# Comparator-Sampler.net
KiCad netlist of a schematic drawn in Altium Designer
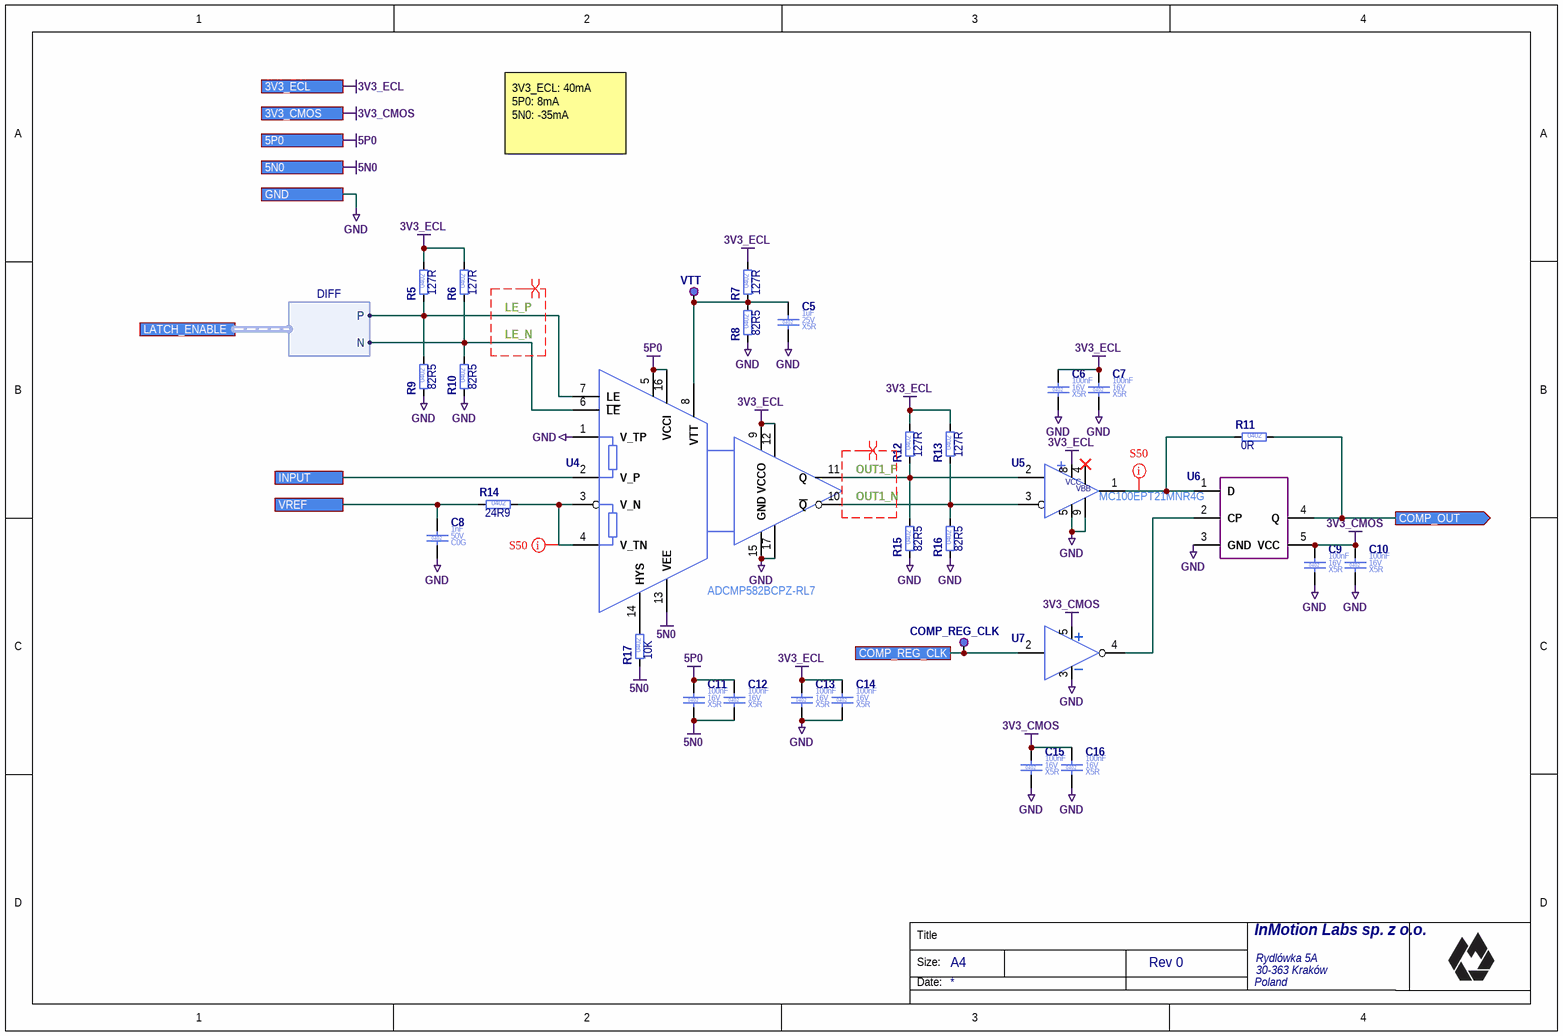
[diagram p0: Comparator-Sampler.SchDoc]

(export (version "E")
  (design (tool "Eeschema 10.0.6"))
  (components
    (comp (ref "C5")
      (value "C_1UF_25V_X5R_0402_10")
      (footprint "C_0402_1005")
      (description "Ceramic Capacitor")
      (fields
        (field (name "CASE/PACKAGE") "0402")
        (field (name "VOLTAGE RATING (DC)") "25V")
        (field (name "DIELECTRIC") "X5R")
        (field (name "CAPACITANCE") "1uF")
        (field (name "TOLERANCE") "10%")
        (field (name "MANUFACTURER PART NUMBER") "CL05A105KA5NQNC")
      )
      (libsource (lib "7Sigma") (part "C"))
    )
    (comp (ref "C6")
      (value "C_100NF_16V_X5R_0402_10")
      (footprint "C_0402_1005")
      (description "Ceramic Capacitor")
      (fields
        (field (name "CASE/PACKAGE") "0402")
        (field (name "VOLTAGE RATING (DC)") "16V")
        (field (name "DIELECTRIC") "X5R")
        (field (name "CAPACITANCE") "100nF")
        (field (name "TOLERANCE") "10%")
        (field (name "MANUFACTURER PART NUMBER") "EMK105BJ104KV-F")
      )
      (libsource (lib "7Sigma") (part "C"))
    )
    (comp (ref "C7")
      (value "C_100NF_16V_X5R_0402_10")
      (footprint "C_0402_1005")
      (description "Ceramic Capacitor")
      (fields
        (field (name "CASE/PACKAGE") "0402")
        (field (name "VOLTAGE RATING (DC)") "16V")
        (field (name "DIELECTRIC") "X5R")
        (field (name "CAPACITANCE") "100nF")
        (field (name "TOLERANCE") "10%")
        (field (name "MANUFACTURER PART NUMBER") "EMK105BJ104KV-F")
      )
      (libsource (lib "7Sigma") (part "C"))
    )
    (comp (ref "C8")
      (value "C_1NF_50V_C0G_0402_5")
      (footprint "C_0402_1005")
      (description "Ceramic Capacitor")
      (fields
        (field (name "CASE/PACKAGE") "0402")
        (field (name "VOLTAGE RATING (DC)") "50V")
        (field (name "DIELECTRIC") "C0G")
        (field (name "CAPACITANCE") "1nF")
        (field (name "TOLERANCE") "5%")
        (field (name "MANUFACTURER PART NUMBER") "UMK105CG102JV-F")
      )
      (libsource (lib "7Sigma") (part "C"))
    )
    (comp (ref "C9")
      (value "C_100NF_16V_X5R_0402_10")
      (footprint "C_0402_1005")
      (description "Ceramic Capacitor")
      (fields
        (field (name "CASE/PACKAGE") "0402")
        (field (name "VOLTAGE RATING (DC)") "16V")
        (field (name "DIELECTRIC") "X5R")
        (field (name "CAPACITANCE") "100nF")
        (field (name "TOLERANCE") "10%")
        (field (name "MANUFACTURER PART NUMBER") "EMK105BJ104KV-F")
      )
      (libsource (lib "7Sigma") (part "C"))
    )
    (comp (ref "C10")
      (value "C_100NF_16V_X5R_0402_10")
      (footprint "C_0402_1005")
      (description "Ceramic Capacitor")
      (fields
        (field (name "CASE/PACKAGE") "0402")
        (field (name "VOLTAGE RATING (DC)") "16V")
        (field (name "DIELECTRIC") "X5R")
        (field (name "CAPACITANCE") "100nF")
        (field (name "TOLERANCE") "10%")
        (field (name "MANUFACTURER PART NUMBER") "EMK105BJ104KV-F")
      )
      (libsource (lib "7Sigma") (part "C"))
    )
    (comp (ref "C11")
      (value "C_100NF_16V_X5R_0402_10")
      (footprint "C_0402_1005")
      (description "Ceramic Capacitor")
      (fields
        (field (name "CASE/PACKAGE") "0402")
        (field (name "VOLTAGE RATING (DC)") "16V")
        (field (name "DIELECTRIC") "X5R")
        (field (name "CAPACITANCE") "100nF")
        (field (name "TOLERANCE") "10%")
        (field (name "MANUFACTURER PART NUMBER") "EMK105BJ104KV-F")
      )
      (libsource (lib "7Sigma") (part "C"))
    )
    (comp (ref "C12")
      (value "C_100NF_16V_X5R_0402_10")
      (footprint "C_0402_1005")
      (description "Ceramic Capacitor")
      (fields
        (field (name "CASE/PACKAGE") "0402")
        (field (name "VOLTAGE RATING (DC)") "16V")
        (field (name "DIELECTRIC") "X5R")
        (field (name "CAPACITANCE") "100nF")
        (field (name "TOLERANCE") "10%")
        (field (name "MANUFACTURER PART NUMBER") "EMK105BJ104KV-F")
      )
      (libsource (lib "7Sigma") (part "C"))
    )
    (comp (ref "C13")
      (value "C_100NF_16V_X5R_0402_10")
      (footprint "C_0402_1005")
      (description "Ceramic Capacitor")
      (fields
        (field (name "CASE/PACKAGE") "0402")
        (field (name "VOLTAGE RATING (DC)") "16V")
        (field (name "DIELECTRIC") "X5R")
        (field (name "CAPACITANCE") "100nF")
        (field (name "TOLERANCE") "10%")
        (field (name "MANUFACTURER PART NUMBER") "EMK105BJ104KV-F")
      )
      (libsource (lib "7Sigma") (part "C"))
    )
    (comp (ref "C14")
      (value "C_100NF_16V_X5R_0402_10")
      (footprint "C_0402_1005")
      (description "Ceramic Capacitor")
      (fields
        (field (name "CASE/PACKAGE") "0402")
        (field (name "VOLTAGE RATING (DC)") "16V")
        (field (name "DIELECTRIC") "X5R")
        (field (name "CAPACITANCE") "100nF")
        (field (name "TOLERANCE") "10%")
        (field (name "MANUFACTURER PART NUMBER") "EMK105BJ104KV-F")
      )
      (libsource (lib "7Sigma") (part "C"))
    )
    (comp (ref "C15")
      (value "C_100NF_16V_X5R_0402_10")
      (footprint "C_0402_1005")
      (description "Ceramic Capacitor")
      (fields
        (field (name "CASE/PACKAGE") "0402")
        (field (name "VOLTAGE RATING (DC)") "16V")
        (field (name "DIELECTRIC") "X5R")
        (field (name "CAPACITANCE") "100nF")
        (field (name "TOLERANCE") "10%")
        (field (name "MANUFACTURER PART NUMBER") "EMK105BJ104KV-F")
      )
      (libsource (lib "7Sigma") (part "C"))
    )
    (comp (ref "C16")
      (value "C_100NF_16V_X5R_0402_10")
      (footprint "C_0402_1005")
      (description "Ceramic Capacitor")
      (fields
        (field (name "CASE/PACKAGE") "0402")
        (field (name "VOLTAGE RATING (DC)") "16V")
        (field (name "DIELECTRIC") "X5R")
        (field (name "CAPACITANCE") "100nF")
        (field (name "TOLERANCE") "10%")
        (field (name "MANUFACTURER PART NUMBER") "EMK105BJ104KV-F")
      )
      (libsource (lib "7Sigma") (part "C"))
    )
    (comp (ref "COMP_REG_CLK")
      (value "TP_PAD_1.3MM")
      (footprint "TP_PAD_1.3MM")
      (description "Testpoint SMD 1.3mm")
      (libsource (lib "7Sigma") (part "TESTPOINT"))
    )
    (comp (ref "R5")
      (value "R_127R_0402_1")
      (footprint "R_0402_1005")
      (description "Thick Film Resistor")
      (fields
        (field (name "RESISTANCE") "127R")
        (field (name "CASE/PACKAGE") "0402")
        (field (name "TOLERANCE") "1%")
        (field (name "MANUFACTURER") "Yageo")
      )
      (libsource (lib "7Sigma") (part "R"))
    )
    (comp (ref "R6")
      (value "R_127R_0402_1")
      (footprint "R_0402_1005")
      (description "Thick Film Resistor")
      (fields
        (field (name "RESISTANCE") "127R")
        (field (name "CASE/PACKAGE") "0402")
        (field (name "TOLERANCE") "1%")
        (field (name "MANUFACTURER") "Yageo")
      )
      (libsource (lib "7Sigma") (part "R"))
    )
    (comp (ref "R7")
      (value "R_127R_0402_1")
      (footprint "R_0402_1005")
      (description "Thick Film Resistor")
      (fields
        (field (name "RESISTANCE") "127R")
        (field (name "CASE/PACKAGE") "0402")
        (field (name "TOLERANCE") "1%")
        (field (name "MANUFACTURER") "Yageo")
      )
      (libsource (lib "7Sigma") (part "R"))
    )
    (comp (ref "R8")
      (value "R_82R5_0402_1")
      (footprint "R_0402_1005")
      (description "Thick Film Resistor")
      (fields
        (field (name "RESISTANCE") "82R5")
        (field (name "CASE/PACKAGE") "0402")
        (field (name "TOLERANCE") "1%")
        (field (name "MANUFACTURER") "Yageo")
      )
      (libsource (lib "7Sigma") (part "R"))
    )
    (comp (ref "R9")
      (value "R_82R5_0402_1")
      (footprint "R_0402_1005")
      (description "Thick Film Resistor")
      (fields
        (field (name "RESISTANCE") "82R5")
        (field (name "CASE/PACKAGE") "0402")
        (field (name "TOLERANCE") "1%")
        (field (name "MANUFACTURER") "Yageo")
      )
      (libsource (lib "7Sigma") (part "R"))
    )
    (comp (ref "R10")
      (value "R_82R5_0402_1")
      (footprint "R_0402_1005")
      (description "Thick Film Resistor")
      (fields
        (field (name "RESISTANCE") "82R5")
        (field (name "CASE/PACKAGE") "0402")
        (field (name "TOLERANCE") "1%")
        (field (name "MANUFACTURER") "Yageo")
      )
      (libsource (lib "7Sigma") (part "R"))
    )
    (comp (ref "R11")
      (value "R_0R_0402_1")
      (footprint "R_0402_1005")
      (description "Thick Film Resistor")
      (fields
        (field (name "RESISTANCE") "0R")
        (field (name "CASE/PACKAGE") "0402")
        (field (name "TOLERANCE") "1%")
        (field (name "MANUFACTURER") "Yageo")
      )
      (libsource (lib "7Sigma") (part "R"))
    )
    (comp (ref "R12")
      (value "R_127R_0402_1")
      (footprint "R_0402_1005")
      (description "Thick Film Resistor")
      (fields
        (field (name "RESISTANCE") "127R")
        (field (name "CASE/PACKAGE") "0402")
        (field (name "TOLERANCE") "1%")
        (field (name "MANUFACTURER") "Yageo")
      )
      (libsource (lib "7Sigma") (part "R"))
    )
    (comp (ref "R13")
      (value "R_127R_0402_1")
      (footprint "R_0402_1005")
      (description "Thick Film Resistor")
      (fields
        (field (name "RESISTANCE") "127R")
        (field (name "CASE/PACKAGE") "0402")
        (field (name "TOLERANCE") "1%")
        (field (name "MANUFACTURER") "Yageo")
      )
      (libsource (lib "7Sigma") (part "R"))
    )
    (comp (ref "R14")
      (value "R_24R9_0402_1")
      (footprint "R_0402_1005")
      (description "Thick Film Resistor")
      (fields
        (field (name "RESISTANCE") "24R9")
        (field (name "CASE/PACKAGE") "0402")
        (field (name "TOLERANCE") "1%")
        (field (name "MANUFACTURER") "Yageo")
      )
      (libsource (lib "7Sigma") (part "R"))
    )
    (comp (ref "R15")
      (value "R_82R5_0402_1")
      (footprint "R_0402_1005")
      (description "Thick Film Resistor")
      (fields
        (field (name "RESISTANCE") "82R5")
        (field (name "CASE/PACKAGE") "0402")
        (field (name "TOLERANCE") "1%")
        (field (name "MANUFACTURER") "Yageo")
      )
      (libsource (lib "7Sigma") (part "R"))
    )
    (comp (ref "R16")
      (value "R_82R5_0402_1")
      (footprint "R_0402_1005")
      (description "Thick Film Resistor")
      (fields
        (field (name "RESISTANCE") "82R5")
        (field (name "CASE/PACKAGE") "0402")
        (field (name "TOLERANCE") "1%")
        (field (name "MANUFACTURER") "Yageo")
      )
      (libsource (lib "7Sigma") (part "R"))
    )
    (comp (ref "R17")
      (value "R_10K_0402_1")
      (footprint "R_0402_1005")
      (description "Thick Film Resistor")
      (fields
        (field (name "RESISTANCE") "10K")
        (field (name "CASE/PACKAGE") "0402")
        (field (name "TOLERANCE") "1%")
        (field (name "MANUFACTURER") "Yageo")
      )
      (libsource (lib "7Sigma") (part "R"))
    )
    (comp (ref "U4")
      (value "ADCMP582BCPZ-RL7")
      (footprint "QFN50P300X300X100_HS-17N")
      (description "Single Comparator")
      (fields
        (field (name "MANUFACTURER PART NUMBER") "ADCMP582BCPZ-RL7")
        (field (name "MANUFACTURER") "Analog Devices")
      )
      (libsource (lib "7Sigma") (part "ADCMP582"))
    )
    (comp (ref "U5")
      (value "MC100EPT21MNR4G")
      (footprint "SON50P200X80_HS-9N")
      (description "Differential LVPECL/LVDS/CML to LVTTL/LVCMOS Translator")
      (fields
        (field (name "MANUFACTURER") "ON Semiconductor")
        (field (name "MANUFACTURER PART NUMBER") "MC100EPT21MNR4G")
      )
      (libsource (lib "7Sigma") (part "MC100EPT21"))
    )
    (comp (ref "U6")
      (value "74LVC1G79GV,125")
      (footprint "SOT23-5_SC74A_SOT753_M")
      (description "D Flip Flop Positive Edge Trigger")
      (fields (field (name "MANUFACTURER") "Nexperia"))
      (libsource (lib "7Sigma") (part "74LVC1G79"))
    )
    (comp (ref "U7")
      (value "SN74AHC1G04DBVR")
      (footprint "SOT23-5_SC74A_SOT753_M")
      (description "Inverters Single")
      (fields (field (name "MANUFACTURER") "Texas Instruments"))
      (libsource (lib "7Sigma") (part "SN74AHC1G04DBVR"))
    )
    (comp (ref "VTT")
      (value "TP_PAD_1.3MM")
      (footprint "TP_PAD_1.3MM")
      (description "Testpoint SMD 1.3mm")
      (libsource (lib "7Sigma") (part "TESTPOINT"))
    )
  )
  (nets
    (net (code "2") (name "/COMP_OUT") (class "Default")
      (node (ref "R11") (pin "2") (pinfunction "2_2") (pintype "passive"))
      (node (ref "U6") (pin "4") (pinfunction "Q_4") (pintype "passive"))
    )
    (net (code "3") (name "/COMP_REG_CLK") (class "Default")
      (node (ref "COMP_REG_CLK") (pin "1") (pinfunction "TP_1") (pintype "passive"))
      (node (ref "U7") (pin "2") (pinfunction "2_2") (pintype "passive"))
    )
    (net (code "4") (name "/INPUT") (class "Default")
      (node (ref "U4") (pin "2") (pinfunction "V_P_2") (pintype "passive"))
    )
    (net (code "5") (name "/LE_N") (class "Default")
      (node (ref "R10") (pin "2") (pinfunction "2_2") (pintype "passive"))
      (node (ref "R6") (pin "1") (pinfunction "1_1") (pintype "passive"))
      (node (ref "U4") (pin "6") (pinfunction "LE_6") (pintype "passive"))
    )
    (net (code "6") (name "/LE_P") (class "Default")
      (node (ref "R5") (pin "1") (pinfunction "1_1") (pintype "passive"))
      (node (ref "R9") (pin "2") (pinfunction "2_2") (pintype "passive"))
      (node (ref "U4") (pin "7") (pinfunction "LE_7") (pintype "passive"))
    )
    (net (code "7") (name "/OUT1_N") (class "Default")
      (node (ref "R13") (pin "1") (pinfunction "1_1") (pintype "passive"))
      (node (ref "R16") (pin "2") (pinfunction "2_2") (pintype "passive"))
      (node (ref "U4") (pin "10") (pinfunction "Q_10") (pintype "passive"))
      (node (ref "U5") (pin "3") (pinfunction "D_3") (pintype "passive"))
    )
    (net (code "8") (name "/OUT1_P") (class "Default")
      (node (ref "R12") (pin "1") (pinfunction "1_1") (pintype "passive"))
      (node (ref "R15") (pin "2") (pinfunction "2_2") (pintype "passive"))
      (node (ref "U4") (pin "11") (pinfunction "Q_11") (pintype "passive"))
      (node (ref "U5") (pin "2") (pinfunction "D_2") (pintype "passive"))
    )
    (net (code "9") (name "/VREF") (class "Default")
      (node (ref "C8") (pin "1") (pinfunction "1_1") (pintype "passive"))
      (node (ref "R14") (pin "1") (pinfunction "1_1") (pintype "passive"))
    )
    (net (code "11") (name "3V3_CMOS") (class "Default")
      (node (ref "C10") (pin "1") (pinfunction "1_1") (pintype "passive"))
      (node (ref "C15") (pin "1") (pinfunction "1_1") (pintype "passive"))
      (node (ref "C16") (pin "1") (pinfunction "1_1") (pintype "passive"))
      (node (ref "C9") (pin "1") (pinfunction "1_1") (pintype "passive"))
      (node (ref "U6") (pin "5") (pinfunction "VCC_5") (pintype "passive"))
      (node (ref "U7") (pin "5") (pinfunction "VCC_5") (pintype "passive"))
    )
    (net (code "12") (name "3V3_ECL") (class "Default")
      (node (ref "C13") (pin "1") (pinfunction "1_1") (pintype "passive"))
      (node (ref "C14") (pin "1") (pinfunction "1_1") (pintype "passive"))
      (node (ref "C6") (pin "1") (pinfunction "1_1") (pintype "passive"))
      (node (ref "C7") (pin "1") (pinfunction "1_1") (pintype "passive"))
      (node (ref "R12") (pin "2") (pinfunction "2_2") (pintype "passive"))
      (node (ref "R13") (pin "2") (pinfunction "2_2") (pintype "passive"))
      (node (ref "R5") (pin "2") (pinfunction "2_2") (pintype "passive"))
      (node (ref "R6") (pin "2") (pinfunction "2_2") (pintype "passive"))
      (node (ref "R7") (pin "2") (pinfunction "2_2") (pintype "passive"))
      (node (ref "U4") (pin "12") (pinfunction "VCCO_12") (pintype "passive"))
      (node (ref "U4") (pin "9") (pinfunction "VCCO_9") (pintype "passive"))
      (node (ref "U5") (pin "8") (pinfunction "VDD_8") (pintype "power_in"))
    )
    (net (code "13") (name "5N0") (class "Default")
      (node (ref "C11") (pin "2") (pinfunction "2_2") (pintype "passive"))
      (node (ref "C12") (pin "2") (pinfunction "2_2") (pintype "passive"))
      (node (ref "R17") (pin "1") (pinfunction "1_1") (pintype "passive"))
      (node (ref "U4") (pin "13") (pinfunction "VEE_13") (pintype "passive"))
    )
    (net (code "14") (name "5P0") (class "Default")
      (node (ref "C11") (pin "1") (pinfunction "1_1") (pintype "passive"))
      (node (ref "C12") (pin "1") (pinfunction "1_1") (pintype "passive"))
      (node (ref "U4") (pin "16") (pinfunction "VCCI_16") (pintype "passive"))
      (node (ref "U4") (pin "5") (pinfunction "VCCI_5") (pintype "passive"))
    )
    (net (code "15") (name "GND") (class "Default")
      (node (ref "C10") (pin "2") (pinfunction "2_2") (pintype "passive"))
      (node (ref "C13") (pin "2") (pinfunction "2_2") (pintype "passive"))
      (node (ref "C14") (pin "2") (pinfunction "2_2") (pintype "passive"))
      (node (ref "C15") (pin "2") (pinfunction "2_2") (pintype "passive"))
      (node (ref "C16") (pin "2") (pinfunction "2_2") (pintype "passive"))
      (node (ref "C5") (pin "2") (pinfunction "2_2") (pintype "passive"))
      (node (ref "C6") (pin "2") (pinfunction "2_2") (pintype "passive"))
      (node (ref "C7") (pin "2") (pinfunction "2_2") (pintype "passive"))
      (node (ref "C8") (pin "2") (pinfunction "2_2") (pintype "passive"))
      (node (ref "C9") (pin "2") (pinfunction "2_2") (pintype "passive"))
      (node (ref "R10") (pin "1") (pinfunction "1_1") (pintype "passive"))
      (node (ref "R15") (pin "1") (pinfunction "1_1") (pintype "passive"))
      (node (ref "R16") (pin "1") (pinfunction "1_1") (pintype "passive"))
      (node (ref "R8") (pin "1") (pinfunction "1_1") (pintype "passive"))
      (node (ref "R9") (pin "1") (pinfunction "1_1") (pintype "passive"))
      (node (ref "U4") (pin "1") (pinfunction "V_TP_1") (pintype "passive"))
      (node (ref "U4") (pin "15") (pinfunction "GND_15") (pintype "passive"))
      (node (ref "U4") (pin "17") (pinfunction "GND_17") (pintype "passive"))
      (node (ref "U5") (pin "5") (pinfunction "VSS_5") (pintype "power_in"))
      (node (ref "U5") (pin "9") (pinfunction "VSS_9") (pintype "power_in"))
      (node (ref "U6") (pin "3") (pinfunction "GND_3") (pintype "passive"))
      (node (ref "U7") (pin "3") (pinfunction "GND_3") (pintype "passive"))
    )
    (net (code "16") (name "Net-(U4-HYS)") (class "Default")
      (node (ref "R17") (pin "2") (pinfunction "2_2") (pintype "passive"))
      (node (ref "U4") (pin "14") (pinfunction "HYS_14") (pintype "passive"))
    )
    (net (code "17") (name "Net-(U4-VTT)") (class "Default")
      (node (ref "C5") (pin "1") (pinfunction "1_1") (pintype "passive"))
      (node (ref "R7") (pin "1") (pinfunction "1_1") (pintype "passive"))
      (node (ref "R8") (pin "2") (pinfunction "2_2") (pintype "passive"))
      (node (ref "U4") (pin "8") (pinfunction "VTT_8") (pintype "passive"))
      (node (ref "VTT") (pin "1") (pinfunction "TP_1") (pintype "passive"))
    )
    (net (code "18") (name "Net-(U4-V_N)") (class "Default")
      (node (ref "R14") (pin "2") (pinfunction "2_2") (pintype "passive"))
      (node (ref "U4") (pin "3") (pinfunction "V_N_3") (pintype "passive"))
      (node (ref "U4") (pin "4") (pinfunction "V_TN_4") (pintype "passive"))
    )
    (net (code "19") (name "Net-(U5-OUTA)") (class "Default")
      (node (ref "R11") (pin "1") (pinfunction "1_1") (pintype "passive"))
      (node (ref "U5") (pin "1") (pinfunction "OUTA_1") (pintype "passive"))
      (node (ref "U6") (pin "1") (pinfunction "D_1") (pintype "passive"))
    )
    (net (code "20") (name "Net-(U6-CP)") (class "Default")
      (node (ref "U6") (pin "2") (pinfunction "CP_2") (pintype "passive"))
      (node (ref "U7") (pin "4") (pinfunction "OutY_4") (pintype "passive"))
    )
    (net (code "21") (name "unconnected-(U5-VDD-Pad4)") (class "Default")
      (node (ref "U5") (pin "4") (pinfunction "VDD_4") (pintype "power_in+no_connect"))
    )
    (net (code "22") (name "unconnected-(U7-NC-Pad1)") (class "Default")
      (node (ref "U7") (pin "1") (pinfunction "NC_1") (pintype "passive"))
    )
  )
)
